# seeknobs6_28Apr2022.net
KiCad netlist of a schematic drawn in EAGLE
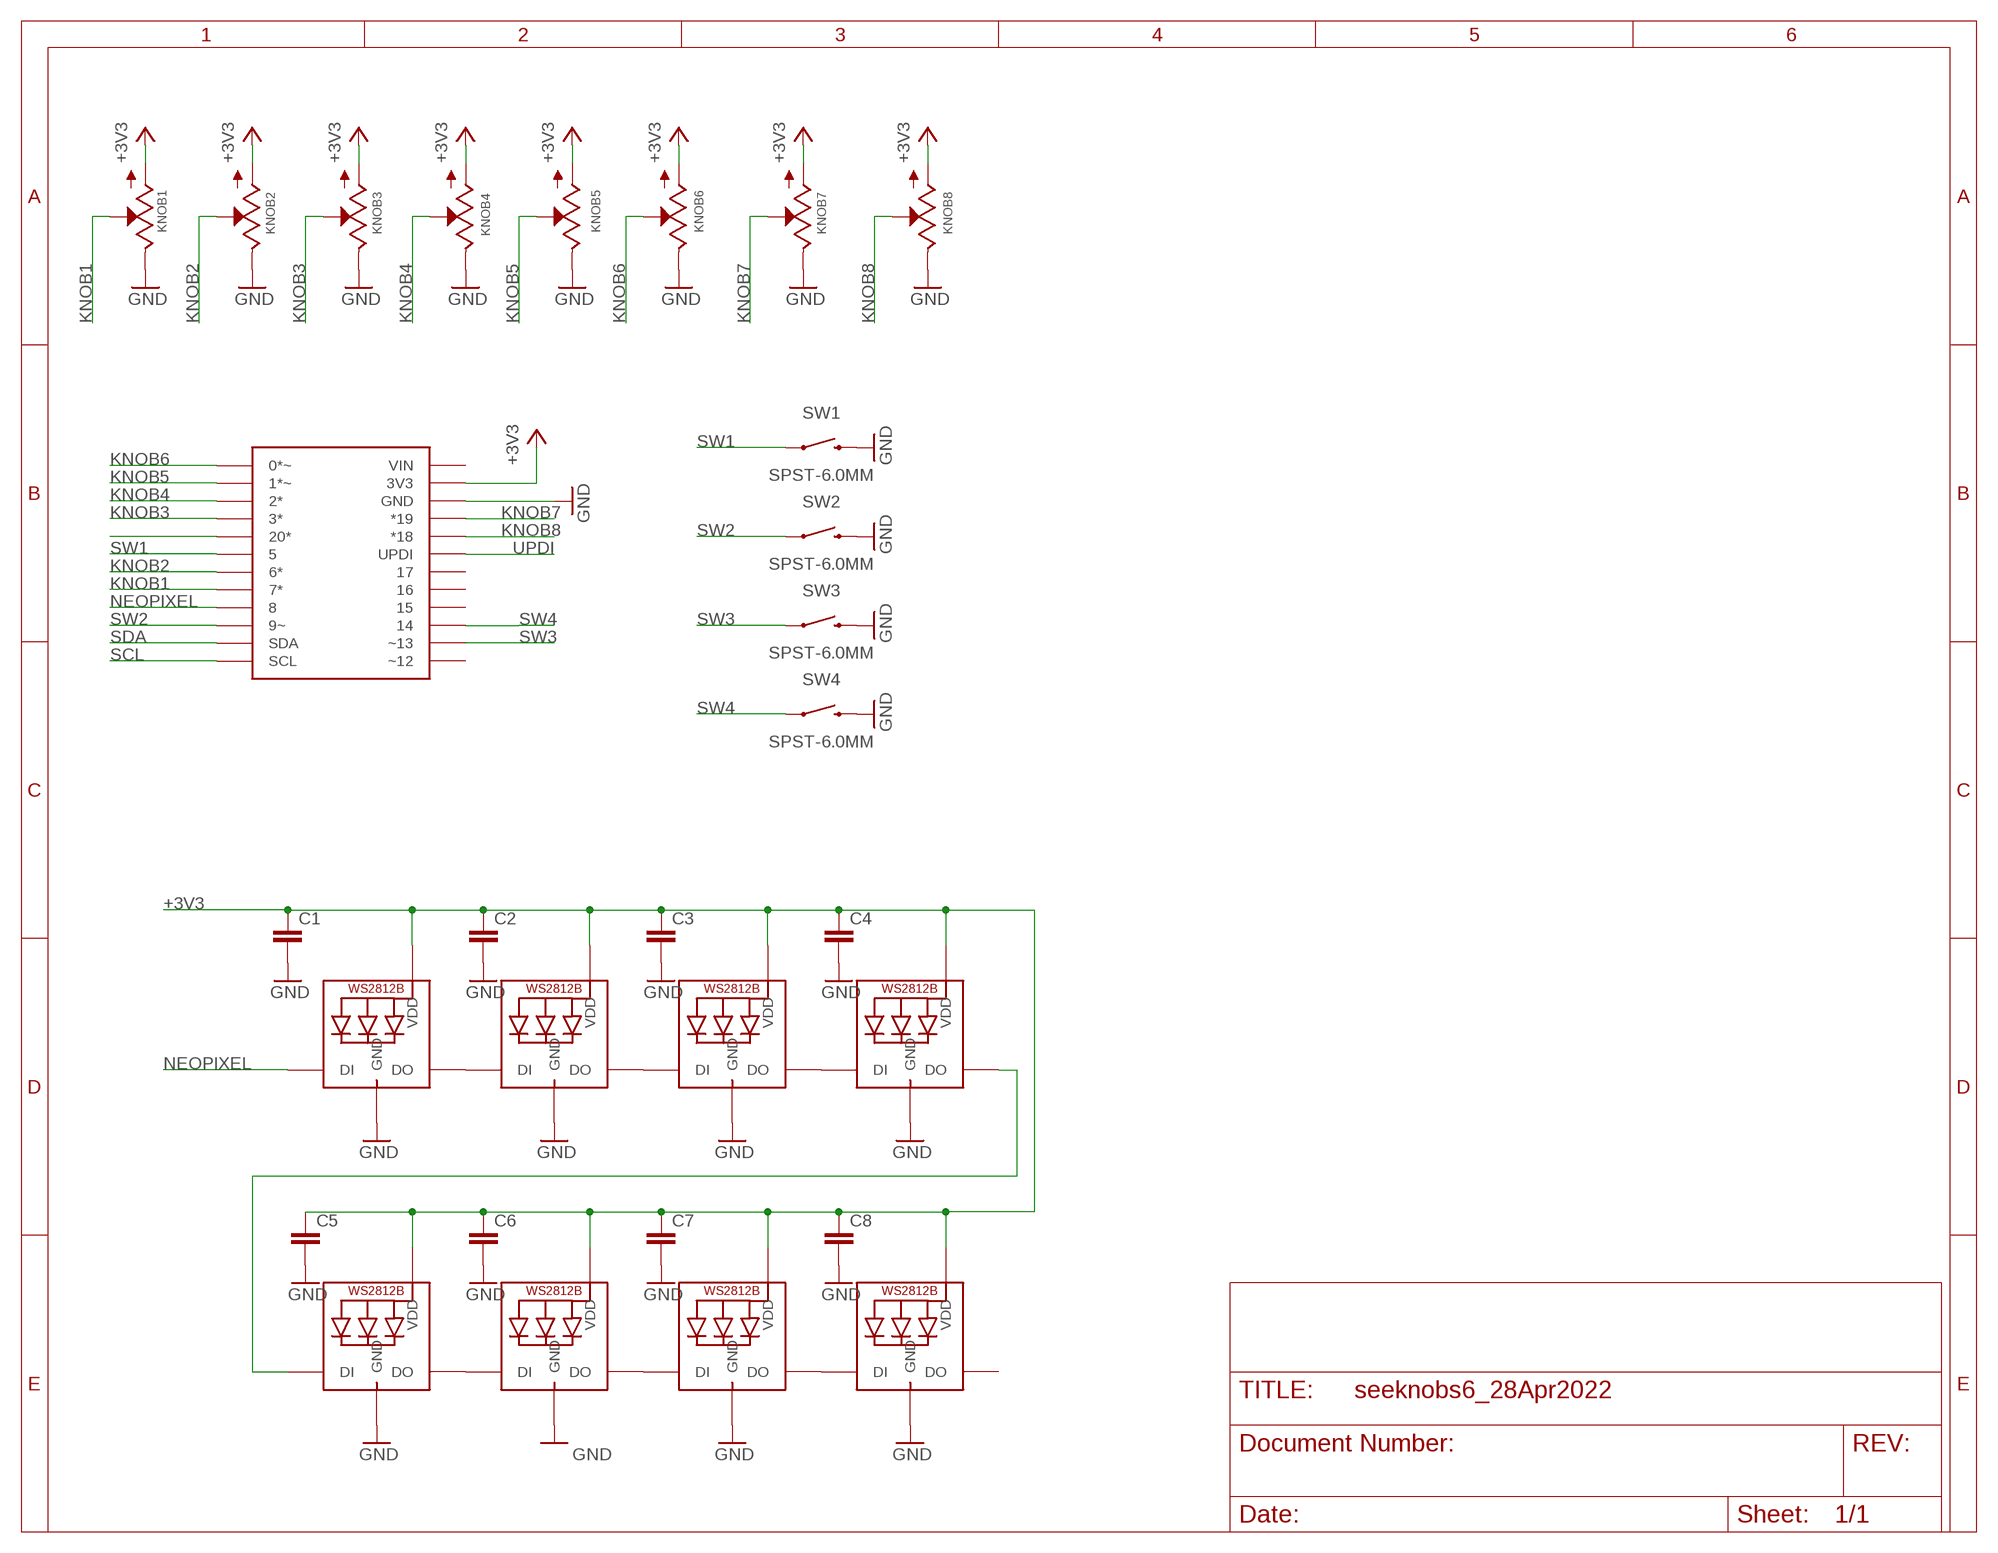
[diagram p0: schematic, sheet 1]

(export (version "E")
  (design (tool "Eeschema 10.0.6"))
  (components
    (comp (ref "C1")
      (value "C-EUC0805")
      (footprint "eagle-import:C0805")
      (libsource (lib "eagle-import") (part "C-EUC0805"))
    )
    (comp (ref "C2")
      (value "C-EUC0805")
      (footprint "eagle-import:C0805")
      (libsource (lib "eagle-import") (part "C-EUC0805"))
    )
    (comp (ref "C3")
      (value "C-EUC0805")
      (footprint "eagle-import:C0805")
      (libsource (lib "eagle-import") (part "C-EUC0805"))
    )
    (comp (ref "C4")
      (value "C-EUC0805")
      (footprint "eagle-import:C0805")
      (libsource (lib "eagle-import") (part "C-EUC0805"))
    )
    (comp (ref "C5")
      (value "C-EUC0805")
      (footprint "eagle-import:C0805")
      (libsource (lib "eagle-import") (part "C-EUC0805"))
    )
    (comp (ref "C6")
      (value "C-EUC0805")
      (footprint "eagle-import:C0805")
      (libsource (lib "eagle-import") (part "C-EUC0805"))
    )
    (comp (ref "C7")
      (value "C-EUC0805")
      (footprint "eagle-import:C0805")
      (libsource (lib "eagle-import") (part "C-EUC0805"))
    )
    (comp (ref "C8")
      (value "C-EUC0805")
      (footprint "eagle-import:C0805")
      (libsource (lib "eagle-import") (part "C-EUC0805"))
    )
    (comp (ref "KNOB1")
      (value "POT")
      (footprint "eagle-import:ALPS_POT")
      (libsource (lib "eagle-import") (part "POT"))
    )
    (comp (ref "KNOB2")
      (value "POT")
      (footprint "eagle-import:ALPS_POT")
      (libsource (lib "eagle-import") (part "POT"))
    )
    (comp (ref "KNOB3")
      (value "POT")
      (footprint "eagle-import:ALPS_POT")
      (libsource (lib "eagle-import") (part "POT"))
    )
    (comp (ref "KNOB4")
      (value "POT")
      (footprint "eagle-import:ALPS_POT")
      (libsource (lib "eagle-import") (part "POT"))
    )
    (comp (ref "KNOB5")
      (value "POT")
      (footprint "eagle-import:ALPS_POT")
      (libsource (lib "eagle-import") (part "POT"))
    )
    (comp (ref "KNOB6")
      (value "POT")
      (footprint "eagle-import:ALPS_POT")
      (libsource (lib "eagle-import") (part "POT"))
    )
    (comp (ref "KNOB7")
      (value "POT")
      (footprint "eagle-import:ALPS_POT")
      (libsource (lib "eagle-import") (part "POT"))
    )
    (comp (ref "KNOB8")
      (value "POT")
      (footprint "eagle-import:ALPS_POT")
      (libsource (lib "eagle-import") (part "POT"))
    )
    (comp (ref "LED1")
      (value "WS2812B5050EZ")
      (footprint "eagle-import:WS2812B-EASY")
      (libsource (lib "eagle-import") (part "WS2812B5050EZ"))
    )
    (comp (ref "LED2")
      (value "WS2812B5050EZ")
      (footprint "eagle-import:WS2812B-EASY")
      (libsource (lib "eagle-import") (part "WS2812B5050EZ"))
    )
    (comp (ref "LED3")
      (value "WS2812B5050EZ")
      (footprint "eagle-import:WS2812B-EASY")
      (libsource (lib "eagle-import") (part "WS2812B5050EZ"))
    )
    (comp (ref "LED4")
      (value "WS2812B5050EZ")
      (footprint "eagle-import:WS2812B-EASY")
      (libsource (lib "eagle-import") (part "WS2812B5050EZ"))
    )
    (comp (ref "LED5")
      (value "WS2812B5050EZ")
      (footprint "eagle-import:WS2812B-EASY")
      (libsource (lib "eagle-import") (part "WS2812B5050EZ"))
    )
    (comp (ref "LED6")
      (value "WS2812B5050EZ")
      (footprint "eagle-import:WS2812B-EASY")
      (libsource (lib "eagle-import") (part "WS2812B5050EZ"))
    )
    (comp (ref "LED7")
      (value "WS2812B5050EZ")
      (footprint "eagle-import:WS2812B-EASY")
      (libsource (lib "eagle-import") (part "WS2812B5050EZ"))
    )
    (comp (ref "LED8")
      (value "WS2812B5050EZ")
      (footprint "eagle-import:WS2812B-EASY")
      (libsource (lib "eagle-import") (part "WS2812B5050EZ"))
    )
    (comp (ref "SEESAW")
      (value "ADAFRUIT_SEESAW_ATTINY817")
      (footprint "eagle-import:ADAFRUIT_SEESAW_ATTINY817")
      (libsource (lib "eagle-import") (part "ADAFRUIT_SEESAW_ATTINY817"))
    )
    (comp (ref "SW1")
      (value "SPST-6.0MM")
      (footprint "eagle-import:TACTILE_SWITCH_PTH_6.0MM")
      (libsource (lib "eagle-import") (part "MOMENTARY-SWITCH-SPST-PTH-6.0MM"))
    )
    (comp (ref "SW2")
      (value "SPST-6.0MM")
      (footprint "eagle-import:TACTILE_SWITCH_PTH_6.0MM")
      (libsource (lib "eagle-import") (part "MOMENTARY-SWITCH-SPST-PTH-6.0MM"))
    )
    (comp (ref "SW3")
      (value "SPST-6.0MM")
      (footprint "eagle-import:TACTILE_SWITCH_PTH_6.0MM")
      (libsource (lib "eagle-import") (part "MOMENTARY-SWITCH-SPST-PTH-6.0MM"))
    )
    (comp (ref "SW4")
      (value "SPST-6.0MM")
      (footprint "eagle-import:TACTILE_SWITCH_PTH_6.0MM")
      (libsource (lib "eagle-import") (part "MOMENTARY-SWITCH-SPST-PTH-6.0MM"))
    )
  )
  (nets
    (net (code "1") (name "+3V3") (class "Default")
      (node (ref "C1") (pin "1") (pinfunction "1_1") (pintype "passive"))
      (node (ref "C2") (pin "1") (pinfunction "1_1") (pintype "passive"))
      (node (ref "C3") (pin "1") (pinfunction "1_1") (pintype "passive"))
      (node (ref "C4") (pin "1") (pinfunction "1_1") (pintype "passive"))
      (node (ref "C5") (pin "1") (pinfunction "1_1") (pintype "passive"))
      (node (ref "C6") (pin "1") (pinfunction "1_1") (pintype "passive"))
      (node (ref "C7") (pin "1") (pinfunction "1_1") (pintype "passive"))
      (node (ref "C8") (pin "1") (pinfunction "1_1") (pintype "passive"))
      (node (ref "KNOB1") (pin "P$3") (pinfunction "A_P$3") (pintype "passive"))
      (node (ref "KNOB2") (pin "P$3") (pinfunction "A_P$3") (pintype "passive"))
      (node (ref "KNOB3") (pin "P$3") (pinfunction "A_P$3") (pintype "passive"))
      (node (ref "KNOB4") (pin "P$3") (pinfunction "A_P$3") (pintype "passive"))
      (node (ref "KNOB5") (pin "P$3") (pinfunction "A_P$3") (pintype "passive"))
      (node (ref "KNOB6") (pin "P$3") (pinfunction "A_P$3") (pintype "passive"))
      (node (ref "KNOB7") (pin "P$3") (pinfunction "A_P$3") (pintype "passive"))
      (node (ref "KNOB8") (pin "P$3") (pinfunction "A_P$3") (pintype "passive"))
      (node (ref "LED1") (pin "1-VDD") (pinfunction "VDD_1-VDD") (pintype "power_in"))
      (node (ref "LED2") (pin "1-VDD") (pinfunction "VDD_1-VDD") (pintype "power_in"))
      (node (ref "LED3") (pin "1-VDD") (pinfunction "VDD_1-VDD") (pintype "power_in"))
      (node (ref "LED4") (pin "1-VDD") (pinfunction "VDD_1-VDD") (pintype "power_in"))
      (node (ref "LED5") (pin "1-VDD") (pinfunction "VDD_1-VDD") (pintype "power_in"))
      (node (ref "LED6") (pin "1-VDD") (pinfunction "VDD_1-VDD") (pintype "power_in"))
      (node (ref "LED7") (pin "1-VDD") (pinfunction "VDD_1-VDD") (pintype "power_in"))
      (node (ref "LED8") (pin "1-VDD") (pinfunction "VDD_1-VDD") (pintype "power_in"))
      (node (ref "SEESAW") (pin "P23") (pinfunction "3V3_P23") (pintype "bidirectional"))
    )
    (net (code "2") (name "/KNOB1") (class "Default")
      (node (ref "KNOB1") (pin "P$2") (pinfunction "S_P$2") (pintype "passive"))
      (node (ref "SEESAW") (pin "P8") (pinfunction "7*_P8") (pintype "bidirectional"))
    )
    (net (code "3") (name "/KNOB2") (class "Default")
      (node (ref "KNOB2") (pin "P$2") (pinfunction "S_P$2") (pintype "passive"))
      (node (ref "SEESAW") (pin "P7") (pinfunction "6*_P7") (pintype "bidirectional"))
    )
    (net (code "4") (name "/KNOB3") (class "Default")
      (node (ref "KNOB3") (pin "P$2") (pinfunction "S_P$2") (pintype "passive"))
      (node (ref "SEESAW") (pin "P4") (pinfunction "3*_P4") (pintype "bidirectional"))
    )
    (net (code "5") (name "/KNOB4") (class "Default")
      (node (ref "KNOB4") (pin "P$2") (pinfunction "S_P$2") (pintype "passive"))
      (node (ref "SEESAW") (pin "P3") (pinfunction "2*_P3") (pintype "bidirectional"))
    )
    (net (code "6") (name "/KNOB5") (class "Default")
      (node (ref "KNOB5") (pin "P$2") (pinfunction "S_P$2") (pintype "passive"))
      (node (ref "SEESAW") (pin "P2") (pinfunction "1*~{}_P2") (pintype "bidirectional"))
    )
    (net (code "7") (name "/KNOB6") (class "Default")
      (node (ref "KNOB6") (pin "P$2") (pinfunction "S_P$2") (pintype "passive"))
      (node (ref "SEESAW") (pin "0") (pinfunction "0*~{}_0") (pintype "bidirectional"))
    )
    (net (code "8") (name "/KNOB7") (class "Default")
      (node (ref "KNOB7") (pin "P$2") (pinfunction "S_P$2") (pintype "passive"))
      (node (ref "SEESAW") (pin "P21") (pinfunction "*19_P21") (pintype "bidirectional"))
    )
    (net (code "9") (name "/KNOB8") (class "Default")
      (node (ref "KNOB8") (pin "P$2") (pinfunction "S_P$2") (pintype "passive"))
      (node (ref "SEESAW") (pin "P20") (pinfunction "*18_P20") (pintype "bidirectional"))
    )
    (net (code "10") (name "/NEOPIXEL") (class "Default")
      (node (ref "LED1") (pin "4-DIN") (pinfunction "DI_4-DIN") (pintype "input"))
      (node (ref "SEESAW") (pin "P9") (pinfunction "8_P9") (pintype "bidirectional"))
    )
    (net (code "11") (name "/SCL") (class "Default")
      (node (ref "SEESAW") (pin "P12") (pinfunction "SCL_P12") (pintype "bidirectional"))
    )
    (net (code "12") (name "/SDA") (class "Default")
      (node (ref "SEESAW") (pin "P11") (pinfunction "SDA_P11") (pintype "bidirectional"))
    )
    (net (code "13") (name "/SW1") (class "Default")
      (node (ref "SEESAW") (pin "P6") (pinfunction "5_P6") (pintype "bidirectional"))
      (node (ref "SW1") (pin "1") (pinfunction "1_1") (pintype "passive"))
    )
    (net (code "14") (name "/SW2") (class "Default")
      (node (ref "SEESAW") (pin "P10") (pinfunction "9~{}_P10") (pintype "bidirectional"))
      (node (ref "SW2") (pin "1") (pinfunction "1_1") (pintype "passive"))
    )
    (net (code "15") (name "/SW3") (class "Default")
      (node (ref "SEESAW") (pin "P14") (pinfunction "~{13}_P14") (pintype "bidirectional"))
      (node (ref "SW3") (pin "1") (pinfunction "1_1") (pintype "passive"))
    )
    (net (code "16") (name "/SW4") (class "Default")
      (node (ref "SEESAW") (pin "P15") (pinfunction "14_P15") (pintype "bidirectional"))
      (node (ref "SW4") (pin "1") (pinfunction "1_1") (pintype "passive"))
    )
    (net (code "17") (name "/UPDI") (class "Default")
      (node (ref "SEESAW") (pin "P19") (pinfunction "UPDI_P19") (pintype "bidirectional"))
    )
    (net (code "18") (name "GND") (class "Default")
      (node (ref "C1") (pin "2") (pinfunction "2_2") (pintype "passive"))
      (node (ref "C2") (pin "2") (pinfunction "2_2") (pintype "passive"))
      (node (ref "C3") (pin "2") (pinfunction "2_2") (pintype "passive"))
      (node (ref "C4") (pin "2") (pinfunction "2_2") (pintype "passive"))
      (node (ref "C5") (pin "2") (pinfunction "2_2") (pintype "passive"))
      (node (ref "C6") (pin "2") (pinfunction "2_2") (pintype "passive"))
      (node (ref "C7") (pin "2") (pinfunction "2_2") (pintype "passive"))
      (node (ref "C8") (pin "2") (pinfunction "2_2") (pintype "passive"))
      (node (ref "KNOB1") (pin "P$1") (pinfunction "E_P$1") (pintype "passive"))
      (node (ref "KNOB2") (pin "P$1") (pinfunction "E_P$1") (pintype "passive"))
      (node (ref "KNOB3") (pin "P$1") (pinfunction "E_P$1") (pintype "passive"))
      (node (ref "KNOB4") (pin "P$1") (pinfunction "E_P$1") (pintype "passive"))
      (node (ref "KNOB5") (pin "P$1") (pinfunction "E_P$1") (pintype "passive"))
      (node (ref "KNOB6") (pin "P$1") (pinfunction "E_P$1") (pintype "passive"))
      (node (ref "KNOB7") (pin "P$1") (pinfunction "E_P$1") (pintype "passive"))
      (node (ref "KNOB8") (pin "P$1") (pinfunction "E_P$1") (pintype "passive"))
      (node (ref "LED1") (pin "3-GND") (pinfunction "GND_3-GND") (pintype "power_in"))
      (node (ref "LED2") (pin "3-GND") (pinfunction "GND_3-GND") (pintype "power_in"))
      (node (ref "LED3") (pin "3-GND") (pinfunction "GND_3-GND") (pintype "power_in"))
      (node (ref "LED4") (pin "3-GND") (pinfunction "GND_3-GND") (pintype "power_in"))
      (node (ref "LED5") (pin "3-GND") (pinfunction "GND_3-GND") (pintype "power_in"))
      (node (ref "LED6") (pin "3-GND") (pinfunction "GND_3-GND") (pintype "power_in"))
      (node (ref "LED7") (pin "3-GND") (pinfunction "GND_3-GND") (pintype "power_in"))
      (node (ref "LED8") (pin "3-GND") (pinfunction "GND_3-GND") (pintype "power_in"))
      (node (ref "SEESAW") (pin "P22") (pinfunction "GND_P22") (pintype "bidirectional"))
      (node (ref "SW1") (pin "3") (pinfunction "2_3") (pintype "passive"))
      (node (ref "SW2") (pin "3") (pinfunction "2_3") (pintype "passive"))
      (node (ref "SW3") (pin "3") (pinfunction "2_3") (pintype "passive"))
      (node (ref "SW4") (pin "3") (pinfunction "2_3") (pintype "passive"))
    )
    (net (code "19") (name "Net-(LED1-DO)") (class "Default")
      (node (ref "LED1") (pin "2-DOUT") (pinfunction "DO_2-DOUT") (pintype "output"))
      (node (ref "LED2") (pin "4-DIN") (pinfunction "DI_4-DIN") (pintype "input"))
    )
    (net (code "20") (name "Net-(LED2-DO)") (class "Default")
      (node (ref "LED2") (pin "2-DOUT") (pinfunction "DO_2-DOUT") (pintype "output"))
      (node (ref "LED3") (pin "4-DIN") (pinfunction "DI_4-DIN") (pintype "input"))
    )
    (net (code "21") (name "Net-(LED3-DO)") (class "Default")
      (node (ref "LED3") (pin "2-DOUT") (pinfunction "DO_2-DOUT") (pintype "output"))
      (node (ref "LED4") (pin "4-DIN") (pinfunction "DI_4-DIN") (pintype "input"))
    )
    (net (code "22") (name "Net-(LED4-DO)") (class "Default")
      (node (ref "LED4") (pin "2-DOUT") (pinfunction "DO_2-DOUT") (pintype "output"))
      (node (ref "LED5") (pin "4-DIN") (pinfunction "DI_4-DIN") (pintype "input"))
    )
    (net (code "23") (name "Net-(LED5-DO)") (class "Default")
      (node (ref "LED5") (pin "2-DOUT") (pinfunction "DO_2-DOUT") (pintype "output"))
      (node (ref "LED6") (pin "4-DIN") (pinfunction "DI_4-DIN") (pintype "input"))
    )
    (net (code "24") (name "Net-(LED6-DO)") (class "Default")
      (node (ref "LED6") (pin "2-DOUT") (pinfunction "DO_2-DOUT") (pintype "output"))
      (node (ref "LED7") (pin "4-DIN") (pinfunction "DI_4-DIN") (pintype "input"))
    )
    (net (code "25") (name "Net-(LED7-DO)") (class "Default")
      (node (ref "LED7") (pin "2-DOUT") (pinfunction "DO_2-DOUT") (pintype "output"))
      (node (ref "LED8") (pin "4-DIN") (pinfunction "DI_4-DIN") (pintype "input"))
    )
    (net (code "26") (name "unconnected-(LED8-DO-Pad2-DOUT)") (class "Default")
      (node (ref "LED8") (pin "2-DOUT") (pinfunction "DO_2-DOUT") (pintype "output"))
    )
    (net (code "27") (name "unconnected-(SEESAW-15-PadP16)") (class "Default")
      (node (ref "SEESAW") (pin "P16") (pinfunction "15_P16") (pintype "bidirectional"))
    )
    (net (code "28") (name "unconnected-(SEESAW-16-PadP17)") (class "Default")
      (node (ref "SEESAW") (pin "P17") (pinfunction "16_P17") (pintype "bidirectional"))
    )
    (net (code "29") (name "unconnected-(SEESAW-17-PadP18)") (class "Default")
      (node (ref "SEESAW") (pin "P18") (pinfunction "17_P18") (pintype "bidirectional"))
    )
    (net (code "30") (name "unconnected-(SEESAW-20*-PadP5)") (class "Default")
      (node (ref "SEESAW") (pin "P5") (pinfunction "20*_P5") (pintype "bidirectional"))
    )
    (net (code "31") (name "unconnected-(SEESAW-VIN-PadP24)") (class "Default")
      (node (ref "SEESAW") (pin "P24") (pinfunction "VIN_P24") (pintype "bidirectional"))
    )
    (net (code "32") (name "unconnected-(SEESAW-~{12}-PadP13)") (class "Default")
      (node (ref "SEESAW") (pin "P13") (pinfunction "~{12}_P13") (pintype "bidirectional"))
    )
  )
)
